# Vorsignal.net
KiCad netlist of a schematic drawn in EAGLE
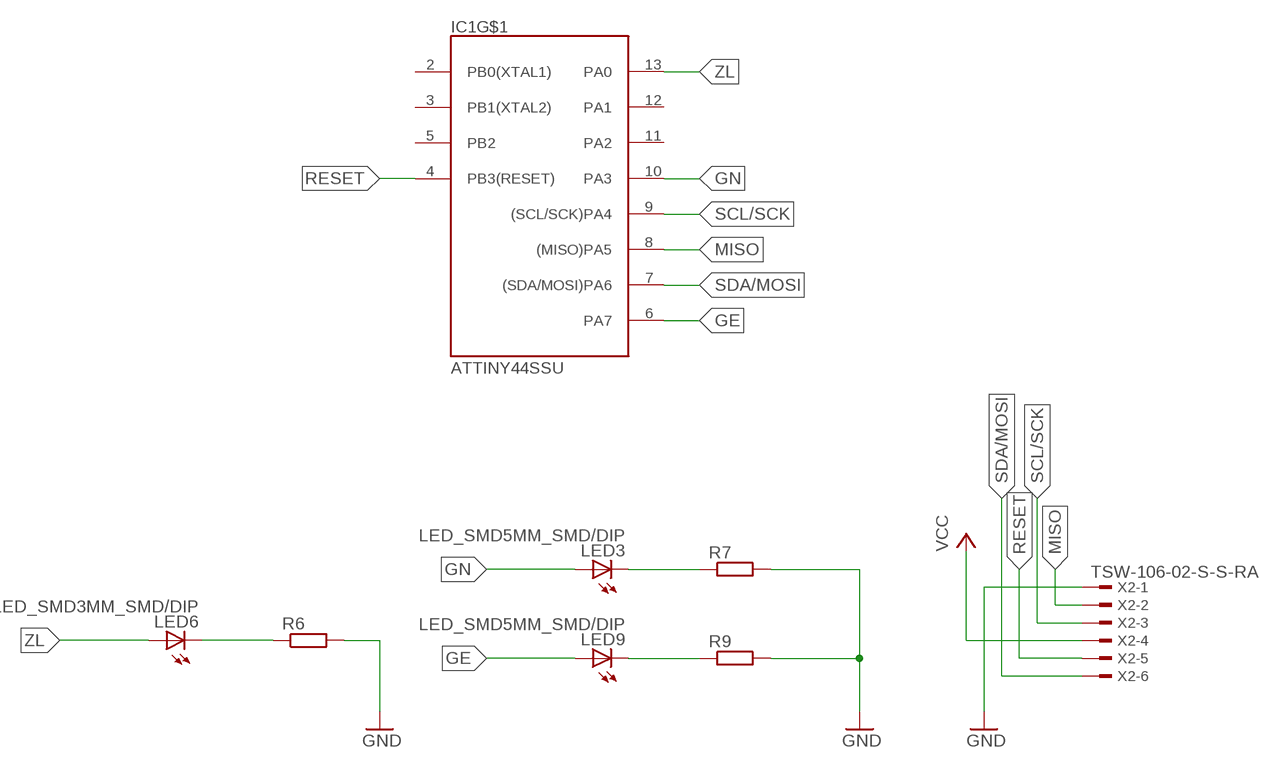
[diagram p0: schematic, sheet 1]

(export (version "E")
  (design (tool "Eeschema 10.0.6"))
  (components
    (comp (ref "IC1")
      (value "ATTINY44SSU")
      (footprint "eagle-import:SO14")
      (libsource (lib "eagle-import") (part "ATTINY44SSU"))
    )
    (comp (ref "LED3")
      (value "LED_SMD5MM_SMD/DIP")
      (footprint "eagle-import:5MM_FLAT_DIP_SMDLED")
      (libsource (lib "eagle-import") (part "LED_SMD5MM_SMD/DIP"))
    )
    (comp (ref "LED6")
      (value "LED_SMD3MM_SMD/DIP")
      (footprint "eagle-import:3MM_FLAT_DIP_SMDLED")
      (libsource (lib "eagle-import") (part "LED_SMD3MM_SMD/DIP"))
    )
    (comp (ref "LED9")
      (value "LED_SMD5MM_SMD/DIP")
      (footprint "eagle-import:5MM_FLAT_DIP_SMDLED")
      (libsource (lib "eagle-import") (part "LED_SMD5MM_SMD/DIP"))
    )
    (comp (ref "R6")
      (value "R-EU_R0603")
      (footprint "eagle-import:R0603")
      (libsource (lib "eagle-import") (part "R-EU_R0603"))
    )
    (comp (ref "R7")
      (value "R-EU_R0603")
      (footprint "eagle-import:R0603")
      (libsource (lib "eagle-import") (part "R-EU_R0603"))
    )
    (comp (ref "R9")
      (value "R-EU_R0603")
      (footprint "eagle-import:R0603")
      (libsource (lib "eagle-import") (part "R-EU_R0603"))
    )
    (comp (ref "X2")
      (value "TSW-106-02-S-S-RA")
      (footprint "eagle-import:TSW-106-02-S-S-RA")
      (libsource (lib "eagle-import") (part "TSW-106-02-S-S-RA"))
    )
  )
  (nets
    (net (code "1") (name "GE") (class "Default")
      (node (ref "IC1") (pin "6") (pinfunction "PA7_6") (pintype "bidirectional"))
      (node (ref "LED9") (pin "+") (pinfunction "A_+") (pintype "passive"))
    )
    (net (code "2") (name "GN") (class "Default")
      (node (ref "IC1") (pin "10") (pinfunction "PA3_10") (pintype "bidirectional"))
      (node (ref "LED3") (pin "+") (pinfunction "A_+") (pintype "passive"))
    )
    (net (code "3") (name "GND") (class "Default")
      (node (ref "R6") (pin "2") (pinfunction "2_2") (pintype "passive"))
      (node (ref "R7") (pin "2") (pinfunction "2_2") (pintype "passive"))
      (node (ref "R9") (pin "2") (pinfunction "2_2") (pintype "passive"))
      (node (ref "X2") (pin "1") (pinfunction "1_1") (pintype "passive"))
    )
    (net (code "4") (name "MISO") (class "Default")
      (node (ref "IC1") (pin "8") (pinfunction "(MISO)PA5_8") (pintype "bidirectional"))
      (node (ref "X2") (pin "2") (pinfunction "1_2") (pintype "passive"))
    )
    (net (code "5") (name "Net-(LED3-C)") (class "Default")
      (node (ref "LED3") (pin "-") (pinfunction "C_-") (pintype "passive"))
      (node (ref "R7") (pin "1") (pinfunction "1_1") (pintype "passive"))
    )
    (net (code "6") (name "Net-(LED6-C)") (class "Default")
      (node (ref "LED6") (pin "-") (pinfunction "C_-") (pintype "passive"))
      (node (ref "R6") (pin "1") (pinfunction "1_1") (pintype "passive"))
    )
    (net (code "7") (name "Net-(LED9-C)") (class "Default")
      (node (ref "LED9") (pin "-") (pinfunction "C_-") (pintype "passive"))
      (node (ref "R9") (pin "1") (pinfunction "1_1") (pintype "passive"))
    )
    (net (code "8") (name "RESET") (class "Default")
      (node (ref "IC1") (pin "4") (pinfunction "PB3(RESET)_4") (pintype "bidirectional"))
      (node (ref "X2") (pin "5") (pinfunction "1_5") (pintype "passive"))
    )
    (net (code "9") (name "SCL{slash}SCK") (class "Default")
      (node (ref "IC1") (pin "9") (pinfunction "(SCL/SCK)PA4_9") (pintype "bidirectional"))
      (node (ref "X2") (pin "3") (pinfunction "1_3") (pintype "passive"))
    )
    (net (code "10") (name "SDA{slash}MOSI") (class "Default")
      (node (ref "IC1") (pin "7") (pinfunction "(SDA/MOSI)PA6_7") (pintype "bidirectional"))
      (node (ref "X2") (pin "6") (pinfunction "1_6") (pintype "passive"))
    )
    (net (code "11") (name "VCC") (class "Default")
      (node (ref "X2") (pin "4") (pinfunction "1_4") (pintype "passive"))
    )
    (net (code "12") (name "ZL") (class "Default")
      (node (ref "IC1") (pin "13") (pinfunction "PA0_13") (pintype "bidirectional"))
      (node (ref "LED6") (pin "+") (pinfunction "A_+") (pintype "passive"))
    )
    (net (code "13") (name "unconnected-(IC1A-PA1-Pad12)") (class "Default")
      (node (ref "IC1") (pin "12") (pinfunction "PA1_12") (pintype "bidirectional"))
    )
    (net (code "14") (name "unconnected-(IC1A-PA2-Pad11)") (class "Default")
      (node (ref "IC1") (pin "11") (pinfunction "PA2_11") (pintype "bidirectional"))
    )
    (net (code "15") (name "unconnected-(IC1A-PB0(XTAL1)-Pad2)") (class "Default")
      (node (ref "IC1") (pin "2") (pinfunction "PB0(XTAL1)_2") (pintype "bidirectional"))
    )
    (net (code "16") (name "unconnected-(IC1A-PB1(XTAL2)-Pad3)") (class "Default")
      (node (ref "IC1") (pin "3") (pinfunction "PB1(XTAL2)_3") (pintype "bidirectional"))
    )
    (net (code "17") (name "unconnected-(IC1A-PB2-Pad5)") (class "Default")
      (node (ref "IC1") (pin "5") (pinfunction "PB2_5") (pintype "bidirectional"))
    )
  )
)
